# 6coils-1-discrete.net
KiCad netlist of a schematic drawn in EasyEDA
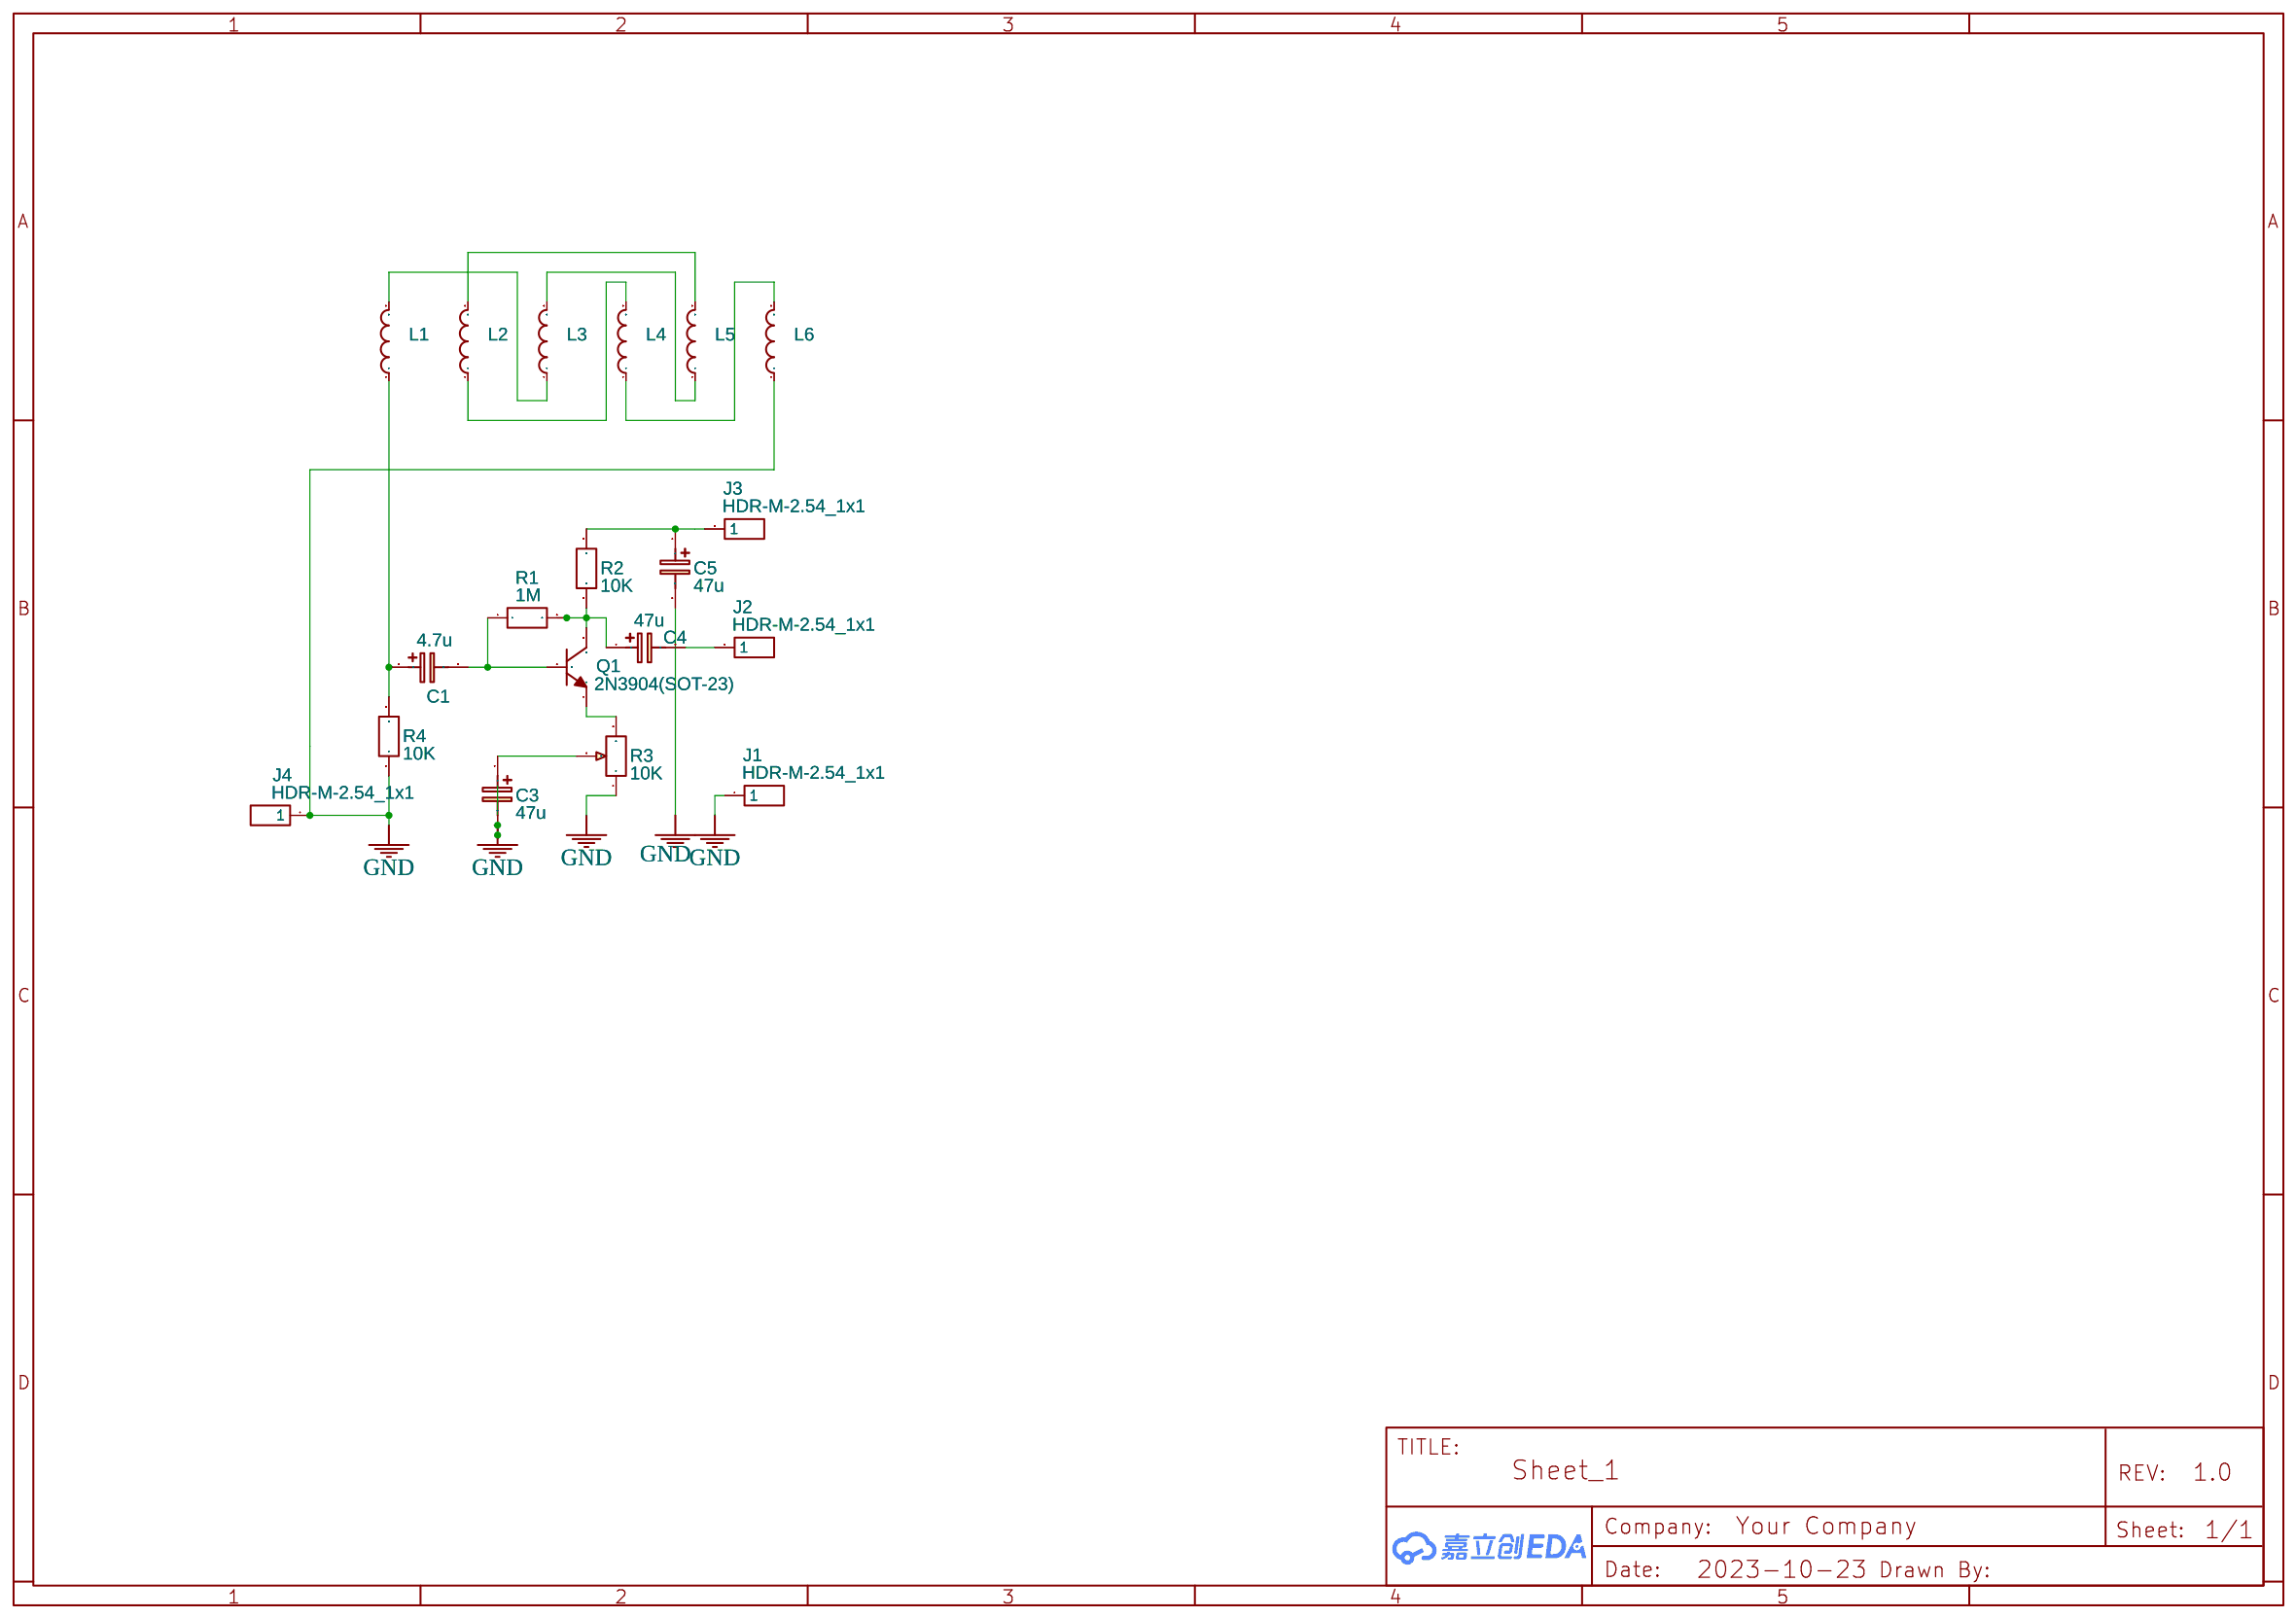
[diagram p0: schematic sheet]

(export (version "E")
  (design (tool "Eeschema 10.0.6"))
  (components
    (comp (ref "C1") (value "4.7u") (libsource (lib "") (part "C_Tan_SMD_A_EU_3")))
    (comp (ref "C3") (value "47u") (libsource (lib "") (part "C_Tan_SMD_A_EU_2")))
    (comp (ref "C4") (value "47u") (libsource (lib "") (part "C_Tan_SMD_A_EU")))
    (comp (ref "C5") (value "47u") (libsource (lib "") (part "C_Tan_SMD_A_EU_1")))
    (comp (ref "J1")
      (value "HDR-M-2.54_1x1")
      (fields (field (name "BOM_Supplier Part") "C81276"))
      (libsource (lib "") (part "HDR-M-2.54_1x1_1"))
    )
    (comp (ref "J2")
      (value "HDR-M-2.54_1x1")
      (fields (field (name "BOM_Supplier Part") "C81276"))
      (libsource (lib "") (part "HDR-M-2.54_1x1_1"))
    )
    (comp (ref "J3")
      (value "HDR-M-2.54_1x1")
      (fields (field (name "BOM_Supplier Part") "C81276"))
      (libsource (lib "") (part "HDR-M-2.54_1x1_1"))
    )
    (comp (ref "J4")
      (value "HDR-M-2.54_1x1")
      (fields (field (name "BOM_Supplier Part") "C81276"))
      (libsource (lib "") (part "HDR-M-2.54_1x1"))
    )
    (comp (ref "L1")
      (value "INDUCTOR_SMD:L_COILCRAFT_XXL4040")
      (fields (field (name "Manufacturer Part") "Inductor_SMD:L_Coilcraft_XxL4040"))
      (libsource (lib "") (part "INDUCTOR_SMD{colon}L_COILCRAFT_XXL4040"))
    )
    (comp (ref "L2")
      (value "INDUCTOR_SMD:L_COILCRAFT_XXL4040")
      (fields (field (name "Manufacturer Part") "Inductor_SMD:L_Coilcraft_XxL4040"))
      (libsource (lib "") (part "INDUCTOR_SMD{colon}L_COILCRAFT_XXL4040"))
    )
    (comp (ref "L3")
      (value "INDUCTOR_SMD:L_COILCRAFT_XXL4040")
      (fields (field (name "Manufacturer Part") "Inductor_SMD:L_Coilcraft_XxL4040"))
      (libsource (lib "") (part "INDUCTOR_SMD{colon}L_COILCRAFT_XXL4040_1"))
    )
    (comp (ref "L4")
      (value "INDUCTOR_SMD:L_COILCRAFT_XXL4040")
      (fields (field (name "Manufacturer Part") "Inductor_SMD:L_Coilcraft_XxL4040"))
      (libsource (lib "") (part "INDUCTOR_SMD{colon}L_COILCRAFT_XXL4040_1"))
    )
    (comp (ref "L5")
      (value "INDUCTOR_SMD:L_COILCRAFT_XXL4040")
      (fields (field (name "Manufacturer Part") "Inductor_SMD:L_Coilcraft_XxL4040"))
      (libsource (lib "") (part "INDUCTOR_SMD{colon}L_COILCRAFT_XXL4040_1"))
    )
    (comp (ref "L6")
      (value "INDUCTOR_SMD:L_COILCRAFT_XXL4040")
      (fields (field (name "Manufacturer Part") "Inductor_SMD:L_Coilcraft_XxL4040"))
      (libsource (lib "") (part "INDUCTOR_SMD{colon}L_COILCRAFT_XXL4040_1"))
    )
    (comp (ref "Q1")
      (value "2N3904(SOT-23)")
      (fields
        (field (name "BOM_Manufacturer Part") "2n3904S-RTK/PS")
        (field (name "BOM_Supplier Part") "C18536")
      )
      (libsource (lib "") (part "2N3904(SOT-23)"))
    )
    (comp (ref "R1") (value "1M") (libsource (lib "") (part "R_0603_EU_1")))
    (comp (ref "R2") (value "10K") (libsource (lib "") (part "R_0603_EU")))
    (comp (ref "R3")
      (value "10K")
      (fields (field (name "Manufacturer Part") "RM063-103 10K") (field (name "Manufacturer") "JML"))
      (libsource (lib "") (part "RM063-103 10K"))
    )
    (comp (ref "R4") (value "10K") (libsource (lib "") (part "R_0603_EU")))
  )
  (nets
    (net (code "1") (name "GND") (class "Default")
      (node (ref "C3") (pin "2") (pinfunction "2_2") (pintype "unspecified"))
      (node (ref "C5") (pin "2") (pinfunction "2_2") (pintype "unspecified"))
      (node (ref "J1") (pin "1") (pinfunction "1_1") (pintype "input"))
      (node (ref "J4") (pin "1") (pinfunction "1_1") (pintype "input"))
      (node (ref "L6") (pin "1") (pinfunction "1_1") (pintype "unspecified"))
      (node (ref "R3") (pin "1") (pinfunction "1_1") (pintype "input"))
      (node (ref "R4") (pin "1") (pinfunction "1_1") (pintype "unspecified"))
    )
    (net (code "2") (name "Net-(C1-Pad1)") (class "Default")
      (node (ref "C1") (pin "1") (pinfunction "1_1") (pintype "unspecified"))
      (node (ref "L1") (pin "1") (pinfunction "1_1") (pintype "unspecified"))
      (node (ref "R4") (pin "2") (pinfunction "2_2") (pintype "unspecified"))
    )
    (net (code "3") (name "Net-(C3-Pad1)") (class "Default")
      (node (ref "C3") (pin "1") (pinfunction "1_1") (pintype "unspecified"))
      (node (ref "R3") (pin "2") (pinfunction "2_2") (pintype "input"))
    )
    (net (code "4") (name "Net-(C4-Pad2)") (class "Default")
      (node (ref "C4") (pin "2") (pinfunction "2_2") (pintype "unspecified"))
      (node (ref "J2") (pin "1") (pinfunction "1_1") (pintype "input"))
    )
    (net (code "5") (name "Net-(C5-Pad1)") (class "Default")
      (node (ref "C5") (pin "1") (pinfunction "1_1") (pintype "unspecified"))
      (node (ref "J3") (pin "1") (pinfunction "1_1") (pintype "input"))
      (node (ref "R2") (pin "2") (pinfunction "2_2") (pintype "unspecified"))
    )
    (net (code "6") (name "Net-(L1-Pad2)") (class "Default")
      (node (ref "L1") (pin "2") (pinfunction "2_2") (pintype "unspecified"))
      (node (ref "L3") (pin "1") (pinfunction "1_1") (pintype "unspecified"))
    )
    (net (code "7") (name "Net-(L2-Pad1)") (class "Default")
      (node (ref "L2") (pin "1") (pinfunction "1_1") (pintype "unspecified"))
      (node (ref "L4") (pin "2") (pinfunction "2_2") (pintype "unspecified"))
    )
    (net (code "8") (name "Net-(L2-Pad2)") (class "Default")
      (node (ref "L2") (pin "2") (pinfunction "2_2") (pintype "unspecified"))
      (node (ref "L5") (pin "2") (pinfunction "2_2") (pintype "unspecified"))
    )
    (net (code "9") (name "Net-(L3-Pad2)") (class "Default")
      (node (ref "L3") (pin "2") (pinfunction "2_2") (pintype "unspecified"))
      (node (ref "L5") (pin "1") (pinfunction "1_1") (pintype "unspecified"))
    )
    (net (code "10") (name "Net-(L4-Pad1)") (class "Default")
      (node (ref "L4") (pin "1") (pinfunction "1_1") (pintype "unspecified"))
      (node (ref "L6") (pin "2") (pinfunction "2_2") (pintype "unspecified"))
    )
    (net (code "11") (name "Net-(Q1-B)") (class "Default")
      (node (ref "C1") (pin "2") (pinfunction "2_2") (pintype "unspecified"))
      (node (ref "Q1") (pin "2") (pinfunction "B_2") (pintype "input"))
      (node (ref "R1") (pin "1") (pinfunction "1_1") (pintype "unspecified"))
    )
    (net (code "12") (name "Net-(Q1-C)") (class "Default")
      (node (ref "C4") (pin "1") (pinfunction "1_1") (pintype "unspecified"))
      (node (ref "Q1") (pin "3") (pinfunction "C_3") (pintype "input"))
      (node (ref "R1") (pin "2") (pinfunction "2_2") (pintype "unspecified"))
      (node (ref "R2") (pin "1") (pinfunction "1_1") (pintype "unspecified"))
    )
    (net (code "13") (name "Net-(Q1-E)") (class "Default")
      (node (ref "Q1") (pin "1") (pinfunction "E_1") (pintype "input"))
      (node (ref "R3") (pin "3") (pinfunction "3_3") (pintype "input"))
    )
  )
)
